# ISense.net
KiCad netlist of a schematic drawn in Altium Designer
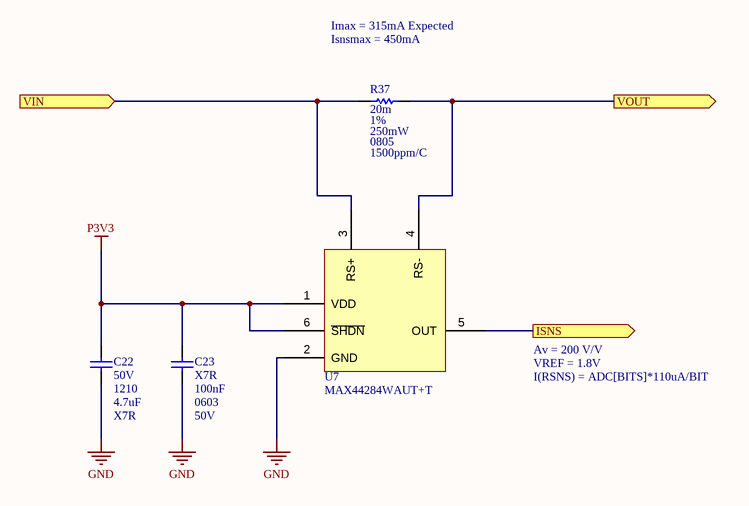
[diagram p0: ISense.SchDoc]

(export (version "E")
  (design (tool "Eeschema 10.0.6"))
  (components
    (comp (ref "C22")
      (value "4.7uF")
      (footprint "CAPC3225X270X30ML30")
      (description "Chip Capacitor, 4.7uF, 10%, 50 V, X7R 1210 (3225 Metric)")
      (fields
        (field (name "VOLTAGE RATING") "50V")
        (field (name "TOLERANCE") "10%")
        (field (name "CASE/PACKAGE") "1210")
        (field (name "DIELECTRIC") "X7R")
        (field (name "Comment") "Capacitor 4.7uF 10%, 50V, X7R, 1210")
      )
      (libsource (lib "Applied Physics Lab") (part "CAP-NP-2"))
    )
    (comp (ref "C23")
      (value "100nF")
      (footprint "CAPC1608X90X40ML10T20")
      (description "Chip Capacitor, 100nF, +/- 10%, 50 V, X7R 0603 (1608 Metric)")
      (fields
        (field (name "DIELECTRIC") "X7R")
        (field (name "CASE/PACKAGE") "0603")
        (field (name "TOLERANCE") "10%")
        (field (name "VOLTAGE RATING") "50V")
        (field (name "Comment") "Capacitor 100nF +/- 10%, 50V, X7R, 0603")
      )
      (libsource (lib "Applied Physics Lab") (part "CAP-NP-2"))
    )
    (comp (ref "R37")
      (value "20m")
      (footprint "RESC2013X50X35ML15T15")
      (description "Chip Resistor, 20 mOhm, +/- 1%, 125 mW, -55 to 125 degC, 0805 (2012 Metric)")
      (fields
        (field (name "POWER") "250mW")
        (field (name "TOLERANCE") "1%")
        (field (name "CASE/PACKAGE") "0805")
        (field (name "TCR") "1500ppm/C")
        (field (name "Comment") "Resistor 20m +/- 1% 0805 250 mW")
      )
      (libsource (lib "Applied Physics Lab") (part "RES-2"))
    )
    (comp (ref "U7")
      (value "MAX44284WAUT+T")
      (footprint "SOT95P280X145-6M")
      (description "-0.1~+36V, High Precision, Low Power Current-Sense Amplifier, 200v/v")
      (libsource (lib "Applied Physics Lab") (part "MAX44284WAUT+T-Symbol-1"))
    )
  )
  (nets
    (net (code "1") (name "/ISNS") (class "Default")
      (node (ref "U7") (pin "5") (pinfunction "OUT_5") (pintype "passive"))
    )
    (net (code "2") (name "/VIN") (class "Default")
      (node (ref "R37") (pin "1") (pinfunction "1_1") (pintype "passive"))
      (node (ref "U7") (pin "3") (pinfunction "RS+_3") (pintype "passive"))
    )
    (net (code "3") (name "/VOUT") (class "Default")
      (node (ref "R37") (pin "2") (pinfunction "2_2") (pintype "passive"))
      (node (ref "U7") (pin "4") (pinfunction "RS-_4") (pintype "passive"))
    )
    (net (code "4") (name "GND") (class "Default")
      (node (ref "C22") (pin "1") (pinfunction "1_1") (pintype "passive"))
      (node (ref "C23") (pin "1") (pinfunction "1_1") (pintype "passive"))
      (node (ref "U7") (pin "2") (pinfunction "GND_2") (pintype "passive"))
    )
    (net (code "5") (name "P3V3") (class "Default")
      (node (ref "C22") (pin "2") (pinfunction "2_2") (pintype "passive"))
      (node (ref "C23") (pin "2") (pinfunction "2_2") (pintype "passive"))
      (node (ref "U7") (pin "1") (pinfunction "VDD_1") (pintype "passive"))
      (node (ref "U7") (pin "6") (pinfunction "~{SHDN}_6") (pintype "passive"))
    )
  )
)
